# POWER.net
KiCad netlist of a schematic drawn in Altium Designer
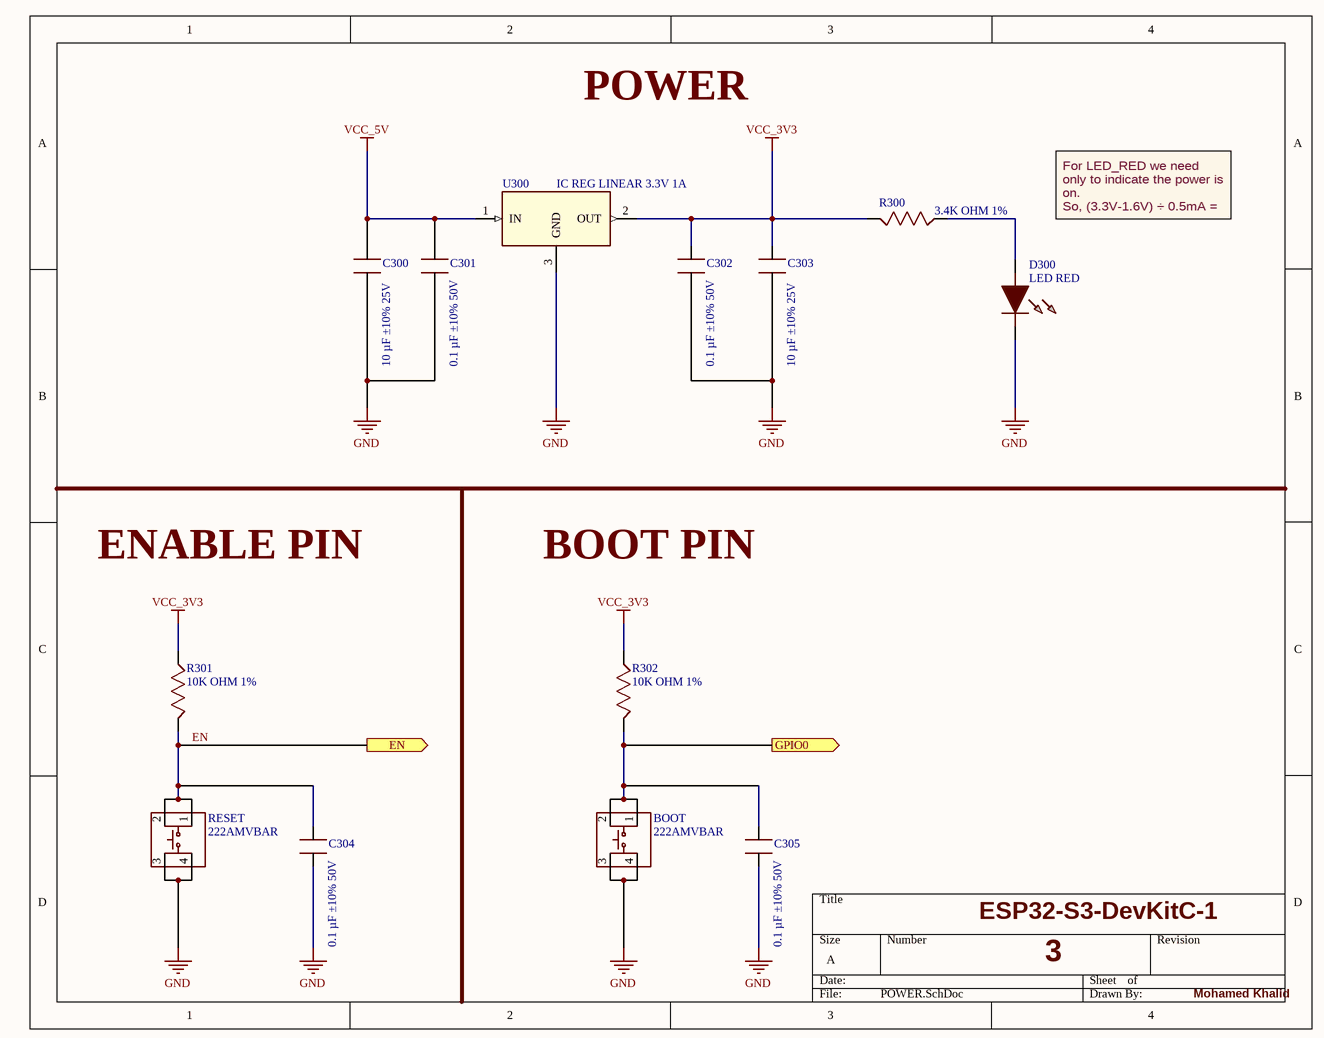
[diagram p0: POWER.SchDoc, right]

(export (version "E")
  (design (tool "Eeschema 10.0.6"))
  (components
    (comp (ref "BOOT")
      (value "222AMVBAR")
      (footprint "222AMVBAR")
      (description "Tactile Switches Gull Wing AF 160gf Act. Dir. Vertical")
      (fields (field (name "MOUSER PART NUMBER") "774-222AMVBAR"))
      (libsource (lib "ESP32_Integrated_Library") (part "222AMVBAR"))
    )
    (comp (ref "C300")
      (value "10 µF ±10% 25V")
      (footprint "CAPC2012X145N")
      (description "10 µF ±10% 25V Ceramic Capacitor X5R 0805 (2012 Metric)")
      (fields (field (name "TOLERANCE") "±10%"))
      (libsource (lib "Schlib") (part "CL21A106KAYNNNE"))
    )
    (comp (ref "C301")
      (value "0.1 µF ±10% 50V")
      (footprint "CAPC1608X90N")
      (description "0.1 µF ±10% 50V Ceramic Capacitor X7R 0603 (1608 Metric)")
      (fields (field (name "TOLERANCE") "±10%"))
      (libsource (lib "ESP32_Integrated_Library") (part "CL10B104KB8NNNC"))
    )
    (comp (ref "C302")
      (value "0.1 µF ±10% 50V")
      (footprint "CAPC1608X90N")
      (description "0.1 µF ±10% 50V Ceramic Capacitor X7R 0603 (1608 Metric)")
      (fields (field (name "TOLERANCE") "±10%"))
      (libsource (lib "ESP32_Integrated_Library") (part "CL10B104KB8NNNC"))
    )
    (comp (ref "C303")
      (value "10 µF ±10% 25V")
      (footprint "CAPC2012X145N")
      (description "10 µF ±10% 25V Ceramic Capacitor X5R 0805 (2012 Metric)")
      (fields (field (name "TOLERANCE") "±10%"))
      (libsource (lib "Schlib") (part "CL21A106KAYNNNE"))
    )
    (comp (ref "C304")
      (value "0.1 µF ±10% 50V")
      (footprint "CAPC1608X90N")
      (description "0.1 µF ±10% 50V Ceramic Capacitor X7R 0603 (1608 Metric)")
      (fields (field (name "TOLERANCE") "±10%"))
      (libsource (lib "ESP32_Integrated_Library") (part "CL10B104KB8NNNC"))
    )
    (comp (ref "C305")
      (value "0.1 µF ±10% 50V")
      (footprint "CAPC1608X90N")
      (description "0.1 µF ±10% 50V Ceramic Capacitor X7R 0603 (1608 Metric)")
      (fields (field (name "TOLERANCE") "±10%"))
      (libsource (lib "ESP32_Integrated_Library") (part "CL10B104KB8NNNC"))
    )
    (comp (ref "D300")
      (value "LED RED")
      (footprint "5988A10107F")
      (description "598 A SMD LED 0402 pkg Red 635nm Low Current 5ma 7\" Reel")
      (libsource (lib "ESP32_Integrated_Library") (part "5988A10107F"))
    )
    (comp (ref "R300")
      (value "3.4K OHM 1%")
      (footprint "RESC2012X65N")
      (description "3.4 kOhms ±1% 0.125W, 1/8W Chip Resistor 0805 (2012 Metric) Automotive AEC-Q200 Thick Film")
      (fields (field (name "TOLERANCE") "±1%"))
      (libsource (lib "ESP32_Integrated_Library") (part "RMCF0805FT3K40"))
    )
    (comp (ref "R301")
      (value "10K OHM 1%")
      (footprint "RESC2012X65N")
      (description "10 kOhms ±1% 0.125W, 1/8W Chip Resistor 0805 (2012 Metric) Automotive AEC-Q200 Thick Film")
      (fields (field (name "TOLERANCE") "±1%"))
      (libsource (lib "ESP32_Integrated_Library") (part "RMCF0805FT10K0"))
    )
    (comp (ref "R302")
      (value "10K OHM 1%")
      (footprint "RESC2012X65N")
      (description "10 kOhms ±1% 0.125W, 1/8W Chip Resistor 0805 (2012 Metric) Automotive AEC-Q200 Thick Film")
      (fields (field (name "TOLERANCE") "±1%"))
      (libsource (lib "ESP32_Integrated_Library") (part "RMCF0805FT10K0"))
    )
    (comp (ref "RESET")
      (value "222AMVBAR")
      (footprint "222AMVBAR")
      (description "Tactile Switches Gull Wing AF 160gf Act. Dir. Vertical")
      (fields (field (name "MOUSER PART NUMBER") "774-222AMVBAR"))
      (libsource (lib "ESP32_Integrated_Library") (part "222AMVBAR"))
    )
    (comp (ref "U300")
      (value "IC REG LINEAR 3.3V 1A")
      (footprint "KC_3_ADI")
      (description "Linear Voltage Regulator IC Positive Fixed 1 Output 1A SOT-223-3")
      (libsource (lib "ESP32_Integrated_Library") (part "ADP3338AKCZ-3.3RL7"))
    )
  )
  (nets
    (net (code "1") (name "/EN") (class "Default")
      (node (ref "C304") (pin "2") (pinfunction "2_2") (pintype "passive"))
      (node (ref "R301") (pin "1") (pinfunction "1_1") (pintype "passive"))
      (node (ref "RESET") (pin "1") (pinfunction "COM_1_1") (pintype "passive"))
      (node (ref "RESET") (pin "2") (pinfunction "NO_1_2") (pintype "passive"))
    )
    (net (code "2") (name "/GPIO0") (class "Default")
      (node (ref "BOOT") (pin "1") (pinfunction "COM_1_1") (pintype "passive"))
      (node (ref "BOOT") (pin "2") (pinfunction "NO_1_2") (pintype "passive"))
      (node (ref "C305") (pin "2") (pinfunction "2_2") (pintype "passive"))
      (node (ref "R302") (pin "1") (pinfunction "1_1") (pintype "passive"))
    )
    (net (code "3") (name "GND") (class "Default")
      (node (ref "BOOT") (pin "3") (pinfunction "COM_2_3") (pintype "passive"))
      (node (ref "BOOT") (pin "4") (pinfunction "NO_2_4") (pintype "passive"))
      (node (ref "C300") (pin "1") (pinfunction "1_1") (pintype "passive"))
      (node (ref "C301") (pin "1") (pinfunction "1_1") (pintype "passive"))
      (node (ref "C302") (pin "1") (pinfunction "1_1") (pintype "passive"))
      (node (ref "C303") (pin "1") (pinfunction "1_1") (pintype "passive"))
      (node (ref "C304") (pin "1") (pinfunction "1_1") (pintype "passive"))
      (node (ref "C305") (pin "1") (pinfunction "1_1") (pintype "passive"))
      (node (ref "D300") (pin "2") (pinfunction "A_2") (pintype "passive"))
      (node (ref "RESET") (pin "3") (pinfunction "COM_2_3") (pintype "passive"))
      (node (ref "RESET") (pin "4") (pinfunction "NO_2_4") (pintype "passive"))
      (node (ref "U300") (pin "3") (pinfunction "GND_3") (pintype "passive"))
    )
    (net (code "4") (name "Net-(D300-K)") (class "Default")
      (node (ref "D300") (pin "1") (pinfunction "K_1") (pintype "passive"))
      (node (ref "R300") (pin "2") (pinfunction "2_2") (pintype "passive"))
    )
    (net (code "5") (name "VCC_3V3") (class "Default")
      (node (ref "C302") (pin "2") (pinfunction "2_2") (pintype "passive"))
      (node (ref "C303") (pin "2") (pinfunction "2_2") (pintype "passive"))
      (node (ref "R300") (pin "1") (pinfunction "1_1") (pintype "passive"))
      (node (ref "R301") (pin "2") (pinfunction "2_2") (pintype "passive"))
      (node (ref "R302") (pin "2") (pinfunction "2_2") (pintype "passive"))
      (node (ref "U300") (pin "2") (pinfunction "OUT_2") (pintype "output"))
    )
    (net (code "6") (name "VCC_5V") (class "Default")
      (node (ref "C300") (pin "2") (pinfunction "2_2") (pintype "passive"))
      (node (ref "C301") (pin "2") (pinfunction "2_2") (pintype "passive"))
      (node (ref "U300") (pin "1") (pinfunction "IN_1") (pintype "input"))
    )
  )
)
